# Debugger_V0_4.net
KiCad netlist of a schematic drawn in EAGLE
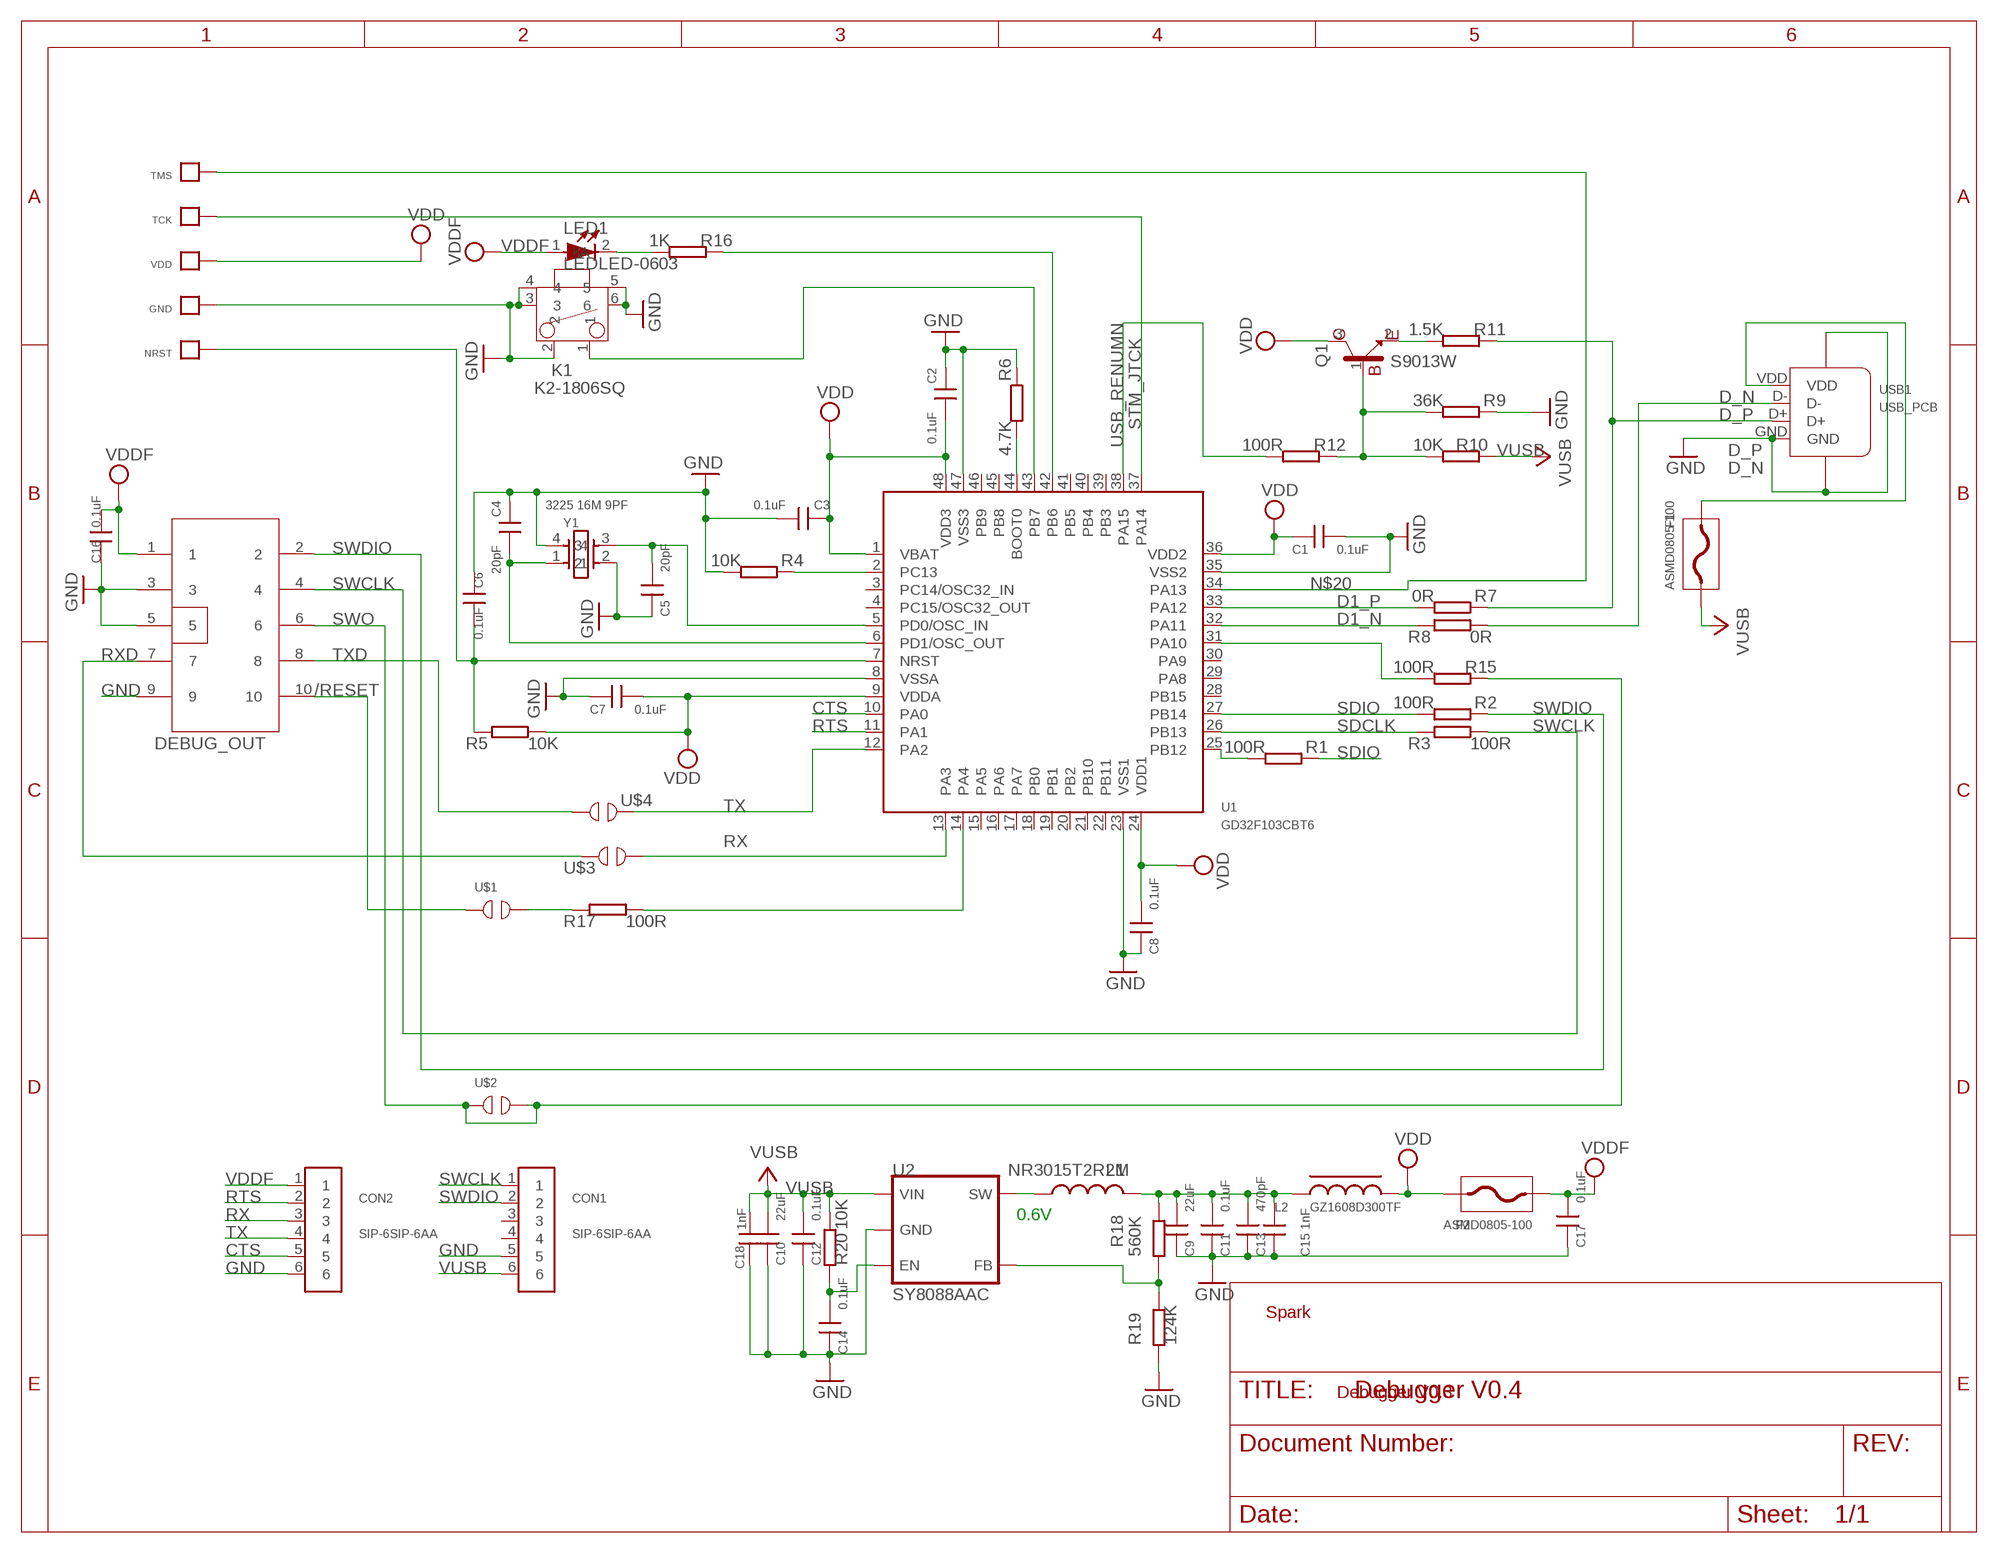
[diagram p0: schematic, sheet 1]

(export (version "E")
  (design (tool "Eeschema 10.0.6"))
  (components
    (comp (ref "C1")
      (value "0.1uF")
      (footprint "eagle-import:C0402")
      (libsource (lib "eagle-import") (part "CAP0402A"))
    )
    (comp (ref "C2")
      (value "0.1uF")
      (footprint "eagle-import:C0402")
      (libsource (lib "eagle-import") (part "CAP0402A"))
    )
    (comp (ref "C3")
      (value "0.1uF")
      (footprint "eagle-import:C0402")
      (libsource (lib "eagle-import") (part "CAP0402A"))
    )
    (comp (ref "C4")
      (value "20pF")
      (footprint "eagle-import:C0402")
      (libsource (lib "eagle-import") (part "CAP0402A"))
    )
    (comp (ref "C5")
      (value "20pF")
      (footprint "eagle-import:C0402")
      (libsource (lib "eagle-import") (part "CAP0402A"))
    )
    (comp (ref "C6")
      (value "0.1uF")
      (footprint "eagle-import:C0402")
      (libsource (lib "eagle-import") (part "CAP0402A"))
    )
    (comp (ref "C7")
      (value "0.1uF")
      (footprint "eagle-import:C0402")
      (libsource (lib "eagle-import") (part "CAP0402A"))
    )
    (comp (ref "C8")
      (value "0.1uF")
      (footprint "eagle-import:C0402")
      (libsource (lib "eagle-import") (part "CAP0402A"))
    )
    (comp (ref "C9")
      (value "22uF")
      (footprint "eagle-import:C0805")
      (libsource (lib "eagle-import") (part "CAPC0805"))
    )
    (comp (ref "C10")
      (value "22uF")
      (footprint "eagle-import:C0805")
      (libsource (lib "eagle-import") (part "CAPC0805"))
    )
    (comp (ref "C11")
      (value "0.1uF")
      (footprint "eagle-import:C0402")
      (libsource (lib "eagle-import") (part "CAP0402A"))
    )
    (comp (ref "C12")
      (value "0.1uF")
      (footprint "eagle-import:C0402")
      (libsource (lib "eagle-import") (part "CAP0402A"))
    )
    (comp (ref "C13")
      (value "470pF")
      (footprint "eagle-import:C0402")
      (libsource (lib "eagle-import") (part "CAP0402A"))
    )
    (comp (ref "C14")
      (value "0.1uF")
      (footprint "eagle-import:C0402")
      (libsource (lib "eagle-import") (part "CAP0402A"))
    )
    (comp (ref "C15")
      (value "1nF")
      (footprint "eagle-import:C0402")
      (libsource (lib "eagle-import") (part "CAP0402A"))
    )
    (comp (ref "C16")
      (value "0.1uF")
      (footprint "eagle-import:C0402")
      (libsource (lib "eagle-import") (part "CAP0402A"))
    )
    (comp (ref "C17")
      (value "0.1uF")
      (footprint "eagle-import:C0402")
      (libsource (lib "eagle-import") (part "CAP0402A"))
    )
    (comp (ref "C18")
      (value "1nF")
      (footprint "eagle-import:C0402")
      (libsource (lib "eagle-import") (part "CAP0402A"))
    )
    (comp (ref "CON1")
      (value "SIP-6SIP-6AA")
      (footprint "eagle-import:PAIZHEN6P_2.54AA")
      (libsource (lib "eagle-import") (part "SIP-6SIP-6AA"))
    )
    (comp (ref "CON2")
      (value "SIP-6SIP-6AA")
      (footprint "eagle-import:PAIZHEN6P_2.54AA")
      (libsource (lib "eagle-import") (part "SIP-6SIP-6AA"))
    )
    (comp (ref "DEBUG_OUT")
      (value "CON5X2")
      (footprint "eagle-import:CON5X2_1.27")
      (libsource (lib "eagle-import") (part "CON5X2"))
    )
    (comp (ref "F1")
      (value "ASMD0805-100")
      (footprint "eagle-import:F0805")
      (libsource (lib "eagle-import") (part "FUSE"))
    )
    (comp (ref "F2")
      (value "ASMD0805-100")
      (footprint "eagle-import:F0805")
      (libsource (lib "eagle-import") (part "FUSE"))
    )
    (comp (ref "GND")
      (value "TPTP")
      (footprint "eagle-import:TP")
      (libsource (lib "eagle-import") (part "TPTP"))
    )
    (comp (ref "K1")
      (value "K2-1806SQ")
      (footprint "eagle-import:K2-1806C")
      (libsource (lib "eagle-import") (part "K2-1806C"))
    )
    (comp (ref "L1")
      (value "NR3015T2R2M")
      (footprint "eagle-import:INDUCTOR-NR3015")
      (libsource (lib "eagle-import") (part "INDUCTORB"))
    )
    (comp (ref "L2")
      (value "GZ1608D300TF")
      (footprint "eagle-import:R-0603A")
      (libsource (lib "eagle-import") (part "L"))
    )
    (comp (ref "LED1")
      (value "LEDLED-0603")
      (footprint "eagle-import:LED-0603")
      (libsource (lib "eagle-import") (part "LEDLED-0603"))
    )
    (comp (ref "NRST")
      (value "TPTP")
      (footprint "eagle-import:TP")
      (libsource (lib "eagle-import") (part "TPTP"))
    )
    (comp (ref "Q1")
      (value "S9013W")
      (footprint "eagle-import:SOT-323")
      (libsource (lib "eagle-import") (part "NPNSOT-323"))
    )
    (comp (ref "R1")
      (value "100R")
      (footprint "eagle-import:R-0402S")
      (libsource (lib "eagle-import") (part "RES0402S"))
    )
    (comp (ref "R2")
      (value "100R")
      (footprint "eagle-import:R-0402S")
      (libsource (lib "eagle-import") (part "RES0402S"))
    )
    (comp (ref "R3")
      (value "100R")
      (footprint "eagle-import:R-0402S")
      (libsource (lib "eagle-import") (part "RES0402S"))
    )
    (comp (ref "R4")
      (value "10K")
      (footprint "eagle-import:R-0402S")
      (libsource (lib "eagle-import") (part "RES0402S"))
    )
    (comp (ref "R5")
      (value "10K")
      (footprint "eagle-import:R-0402S")
      (libsource (lib "eagle-import") (part "RES0402S"))
    )
    (comp (ref "R6")
      (value "4.7K")
      (footprint "eagle-import:R-0402S")
      (libsource (lib "eagle-import") (part "RES0402S"))
    )
    (comp (ref "R7")
      (value "0R")
      (footprint "eagle-import:R-0402S")
      (libsource (lib "eagle-import") (part "RES0402S"))
    )
    (comp (ref "R8")
      (value "0R")
      (footprint "eagle-import:R-0402S")
      (libsource (lib "eagle-import") (part "RES0402S"))
    )
    (comp (ref "R9")
      (value "36K")
      (footprint "eagle-import:R-0402S")
      (libsource (lib "eagle-import") (part "RES0402S"))
    )
    (comp (ref "R10")
      (value "10K")
      (footprint "eagle-import:R-0402S")
      (libsource (lib "eagle-import") (part "RES0402S"))
    )
    (comp (ref "R11")
      (value "1.5K")
      (footprint "eagle-import:R-0402S")
      (libsource (lib "eagle-import") (part "RES0402S"))
    )
    (comp (ref "R12")
      (value "100R")
      (footprint "eagle-import:R-0402S")
      (libsource (lib "eagle-import") (part "RES0402S"))
    )
    (comp (ref "R15")
      (value "100R")
      (footprint "eagle-import:R-0402S")
      (libsource (lib "eagle-import") (part "RES0402S"))
    )
    (comp (ref "R16")
      (value "1K")
      (footprint "eagle-import:R-0402S")
      (libsource (lib "eagle-import") (part "RES0402S"))
    )
    (comp (ref "R17")
      (value "100R")
      (footprint "eagle-import:R-0402S")
      (libsource (lib "eagle-import") (part "RES0402S"))
    )
    (comp (ref "R18")
      (value "560K")
      (footprint "eagle-import:R-0402S")
      (libsource (lib "eagle-import") (part "RES0402S"))
    )
    (comp (ref "R19")
      (value "124K")
      (footprint "eagle-import:R-0402S")
      (libsource (lib "eagle-import") (part "RES0402S"))
    )
    (comp (ref "R20")
      (value "10K")
      (footprint "eagle-import:R-0402S")
      (libsource (lib "eagle-import") (part "RES0402S"))
    )
    (comp (ref "TCK")
      (value "TPTP")
      (footprint "eagle-import:TP")
      (libsource (lib "eagle-import") (part "TPTP"))
    )
    (comp (ref "TMS")
      (value "TPTP")
      (footprint "eagle-import:TP")
      (libsource (lib "eagle-import") (part "TPTP"))
    )
    (comp (ref "U$1")
      (value "TP_OPEN")
      (footprint "eagle-import:TP_OPEN")
      (libsource (lib "eagle-import") (part "TP_OPEN"))
    )
    (comp (ref "U$2")
      (value "TP_OPEN")
      (footprint "eagle-import:TP_OPEN")
      (libsource (lib "eagle-import") (part "TP_OPEN"))
    )
    (comp (ref "U$3")
      (value "TP_OPEN")
      (footprint "eagle-import:TP_OPEN")
      (libsource (lib "eagle-import") (part "TP_OPEN"))
    )
    (comp (ref "U$4")
      (value "TP_OPEN")
      (footprint "eagle-import:TP_OPEN")
      (libsource (lib "eagle-import") (part "TP_OPEN"))
    )
    (comp (ref "U$6")
      (value "SPARK_LOGO..")
      (footprint "eagle-import:SPARK_LOGO")
      (libsource (lib "eagle-import") (part "SPARK_LOGO.."))
    )
    (comp (ref "U1")
      (value "GD32F103CBT6")
      (footprint "eagle-import:LQFP-48-7X7")
      (libsource (lib "eagle-import") (part "STM32F103LQFP48"))
    )
    (comp (ref "U2")
      (value "SY8088AAC")
      (footprint "eagle-import:SOT23-5L")
      (libsource (lib "eagle-import") (part "AX3701ABA"))
    )
    (comp (ref "USB1")
      (value "USB_PCB")
      (footprint "eagle-import:USB_PCB")
      (libsource (lib "eagle-import") (part "USB_PCB"))
    )
    (comp (ref "VDD")
      (value "TPTP")
      (footprint "eagle-import:TP")
      (libsource (lib "eagle-import") (part "TPTP"))
    )
    (comp (ref "Y1")
      (value "3225 16M 9PF")
      (footprint "eagle-import:CRY_3225_SMT")
      (libsource (lib "eagle-import") (part "CRY-3225CRY-3225"))
    )
  )
  (nets
    (net (code "1") (name "/CTS") (class "Default")
      (node (ref "CON2") (pin "5") (pinfunction "5_5") (pintype "bidirectional"))
      (node (ref "U1") (pin "10") (pinfunction "PA0_10") (pintype "bidirectional"))
    )
    (net (code "2") (name "/D1_N") (class "Default")
      (node (ref "R8") (pin "1") (pinfunction "1_1") (pintype "bidirectional"))
      (node (ref "U1") (pin "32") (pinfunction "PA11_32") (pintype "bidirectional"))
    )
    (net (code "3") (name "/D1_P") (class "Default")
      (node (ref "R7") (pin "2") (pinfunction "2_2") (pintype "bidirectional"))
      (node (ref "U1") (pin "33") (pinfunction "PA12_33") (pintype "bidirectional"))
    )
    (net (code "4") (name "/D_N") (class "Default")
      (node (ref "R8") (pin "2") (pinfunction "2_2") (pintype "bidirectional"))
      (node (ref "USB1") (pin "D-") (pinfunction "D-_D-") (pintype "bidirectional"))
    )
    (net (code "5") (name "/D_P") (class "Default")
      (node (ref "R11") (pin "1") (pinfunction "1_1") (pintype "bidirectional"))
      (node (ref "R7") (pin "1") (pinfunction "1_1") (pintype "bidirectional"))
      (node (ref "USB1") (pin "D+") (pinfunction "D+_D+") (pintype "bidirectional"))
    )
    (net (code "6") (name "/N$20") (class "Default")
      (node (ref "TMS") (pin "P$1") (pinfunction "1_P$1") (pintype "bidirectional"))
      (node (ref "U1") (pin "34") (pinfunction "PA13_34") (pintype "bidirectional"))
    )
    (net (code "7") (name "/RTS") (class "Default")
      (node (ref "CON2") (pin "2") (pinfunction "2_2") (pintype "bidirectional"))
      (node (ref "U1") (pin "11") (pinfunction "PA1_11") (pintype "bidirectional"))
    )
    (net (code "8") (name "/RX") (class "Default")
      (node (ref "CON2") (pin "3") (pinfunction "3_3") (pintype "bidirectional"))
      (node (ref "U$3") (pin "2") (pinfunction "2_2") (pintype "bidirectional"))
      (node (ref "U1") (pin "13") (pinfunction "PA3_13") (pintype "bidirectional"))
    )
    (net (code "9") (name "/RXD") (class "Default")
      (node (ref "DEBUG_OUT") (pin "7") (pinfunction "7_7") (pintype "bidirectional"))
      (node (ref "U$3") (pin "1") (pinfunction "1_1") (pintype "bidirectional"))
    )
    (net (code "10") (name "/SDCLK") (class "Default")
      (node (ref "R3") (pin "1") (pinfunction "1_1") (pintype "bidirectional"))
      (node (ref "U1") (pin "26") (pinfunction "PB13_26") (pintype "bidirectional"))
    )
    (net (code "11") (name "/SDIO") (class "Default")
      (node (ref "R1") (pin "1") (pinfunction "1_1") (pintype "bidirectional"))
      (node (ref "R2") (pin "2") (pinfunction "2_2") (pintype "bidirectional"))
      (node (ref "U1") (pin "27") (pinfunction "PB14_27") (pintype "bidirectional"))
    )
    (net (code "12") (name "/STM_JTCK") (class "Default")
      (node (ref "TCK") (pin "P$1") (pinfunction "1_P$1") (pintype "bidirectional"))
      (node (ref "U1") (pin "37") (pinfunction "PA14_37") (pintype "bidirectional"))
    )
    (net (code "13") (name "/SWCLK") (class "Default")
      (node (ref "CON1") (pin "1") (pinfunction "1_1") (pintype "bidirectional"))
      (node (ref "DEBUG_OUT") (pin "4") (pinfunction "4_4") (pintype "bidirectional"))
      (node (ref "R3") (pin "2") (pinfunction "2_2") (pintype "bidirectional"))
    )
    (net (code "14") (name "/SWDIO") (class "Default")
      (node (ref "CON1") (pin "2") (pinfunction "2_2") (pintype "bidirectional"))
      (node (ref "DEBUG_OUT") (pin "2") (pinfunction "2_2") (pintype "bidirectional"))
      (node (ref "R2") (pin "1") (pinfunction "1_1") (pintype "bidirectional"))
    )
    (net (code "15") (name "/SWO") (class "Default")
      (node (ref "DEBUG_OUT") (pin "6") (pinfunction "6_6") (pintype "bidirectional"))
      (node (ref "R15") (pin "1") (pinfunction "1_1") (pintype "bidirectional"))
      (node (ref "U$2") (pin "1") (pinfunction "1_1") (pintype "bidirectional"))
      (node (ref "U$2") (pin "2") (pinfunction "2_2") (pintype "bidirectional"))
    )
    (net (code "16") (name "/TX") (class "Default")
      (node (ref "CON2") (pin "4") (pinfunction "4_4") (pintype "bidirectional"))
      (node (ref "U$4") (pin "1") (pinfunction "1_1") (pintype "bidirectional"))
      (node (ref "U1") (pin "12") (pinfunction "PA2_12") (pintype "bidirectional"))
    )
    (net (code "17") (name "/TXD") (class "Default")
      (node (ref "DEBUG_OUT") (pin "8") (pinfunction "8_8") (pintype "bidirectional"))
      (node (ref "U$4") (pin "2") (pinfunction "2_2") (pintype "bidirectional"))
    )
    (net (code "18") (name "/USB_RENUMN") (class "Default")
      (node (ref "R12") (pin "2") (pinfunction "2_2") (pintype "bidirectional"))
      (node (ref "U1") (pin "38") (pinfunction "PA15_38") (pintype "bidirectional"))
    )
    (net (code "19") (name "/{slash}RESET") (class "Default")
      (node (ref "DEBUG_OUT") (pin "10") (pinfunction "10_10") (pintype "bidirectional"))
      (node (ref "U$1") (pin "1") (pinfunction "1_1") (pintype "bidirectional"))
    )
    (net (code "20") (name "GND") (class "Default")
      (node (ref "C1") (pin "1") (pinfunction "1_1") (pintype "bidirectional"))
      (node (ref "C10") (pin "2") (pinfunction "2_2") (pintype "bidirectional"))
      (node (ref "C11") (pin "2") (pinfunction "2_2") (pintype "bidirectional"))
      (node (ref "C12") (pin "2") (pinfunction "2_2") (pintype "bidirectional"))
      (node (ref "C13") (pin "2") (pinfunction "2_2") (pintype "bidirectional"))
      (node (ref "C14") (pin "2") (pinfunction "2_2") (pintype "bidirectional"))
      (node (ref "C15") (pin "2") (pinfunction "2_2") (pintype "bidirectional"))
      (node (ref "C16") (pin "2") (pinfunction "2_2") (pintype "bidirectional"))
      (node (ref "C17") (pin "2") (pinfunction "2_2") (pintype "bidirectional"))
      (node (ref "C18") (pin "2") (pinfunction "2_2") (pintype "bidirectional"))
      (node (ref "C2") (pin "2") (pinfunction "2_2") (pintype "bidirectional"))
      (node (ref "C3") (pin "1") (pinfunction "1_1") (pintype "bidirectional"))
      (node (ref "C4") (pin "2") (pinfunction "2_2") (pintype "bidirectional"))
      (node (ref "C5") (pin "2") (pinfunction "2_2") (pintype "bidirectional"))
      (node (ref "C6") (pin "2") (pinfunction "2_2") (pintype "bidirectional"))
      (node (ref "C7") (pin "2") (pinfunction "2_2") (pintype "bidirectional"))
      (node (ref "C8") (pin "2") (pinfunction "2_2") (pintype "bidirectional"))
      (node (ref "C9") (pin "2") (pinfunction "2_2") (pintype "bidirectional"))
      (node (ref "CON1") (pin "5") (pinfunction "5_5") (pintype "bidirectional"))
      (node (ref "CON2") (pin "6") (pinfunction "6_6") (pintype "bidirectional"))
      (node (ref "DEBUG_OUT") (pin "3") (pinfunction "3_3") (pintype "bidirectional"))
      (node (ref "DEBUG_OUT") (pin "5") (pinfunction "5_5") (pintype "bidirectional"))
      (node (ref "DEBUG_OUT") (pin "9") (pinfunction "9_9") (pintype "bidirectional"))
      (node (ref "GND") (pin "P$1") (pinfunction "1_P$1") (pintype "bidirectional"))
      (node (ref "K1") (pin "2") (pinfunction "2_2") (pintype "bidirectional"))
      (node (ref "K1") (pin "3") (pinfunction "3_3") (pintype "bidirectional"))
      (node (ref "K1") (pin "4") (pinfunction "4_4") (pintype "bidirectional"))
      (node (ref "K1") (pin "5") (pinfunction "5_5") (pintype "bidirectional"))
      (node (ref "K1") (pin "6") (pinfunction "6_6") (pintype "bidirectional"))
      (node (ref "R19") (pin "1") (pinfunction "1_1") (pintype "bidirectional"))
      (node (ref "R4") (pin "2") (pinfunction "2_2") (pintype "bidirectional"))
      (node (ref "R6") (pin "1") (pinfunction "1_1") (pintype "bidirectional"))
      (node (ref "R9") (pin "1") (pinfunction "1_1") (pintype "bidirectional"))
      (node (ref "U1") (pin "23") (pinfunction "VSS1_23") (pintype "bidirectional"))
      (node (ref "U1") (pin "35") (pinfunction "VSS2_35") (pintype "bidirectional"))
      (node (ref "U1") (pin "47") (pinfunction "VSS3_47") (pintype "bidirectional"))
      (node (ref "U1") (pin "8") (pinfunction "VSSA_8") (pintype "bidirectional"))
      (node (ref "U2") (pin "2") (pinfunction "GND_2") (pintype "power_in"))
      (node (ref "USB1") (pin "GND") (pinfunction "GND_GND") (pintype "bidirectional"))
      (node (ref "USB1") (pin "GND1") (pinfunction "GND1_GND1") (pintype "power_in"))
      (node (ref "USB1") (pin "GND2") (pinfunction "GND2_GND2") (pintype "bidirectional"))
      (node (ref "Y1") (pin "2") (pinfunction "2_2") (pintype "bidirectional"))
      (node (ref "Y1") (pin "4") (pinfunction "4_4") (pintype "bidirectional"))
    )
    (net (code "21") (name "Net-(C11-Pad1)") (class "Default")
      (node (ref "C11") (pin "1") (pinfunction "1_1") (pintype "bidirectional"))
      (node (ref "C13") (pin "1") (pinfunction "1_1") (pintype "bidirectional"))
      (node (ref "C15") (pin "1") (pinfunction "1_1") (pintype "bidirectional"))
      (node (ref "C9") (pin "1") (pinfunction "1_1") (pintype "bidirectional"))
      (node (ref "L1") (pin "2") (pinfunction "2_2") (pintype "passive"))
      (node (ref "L2") (pin "1") (pinfunction "1_1") (pintype "bidirectional"))
      (node (ref "R18") (pin "2") (pinfunction "2_2") (pintype "bidirectional"))
    )
    (net (code "22") (name "Net-(F1-2)") (class "Default")
      (node (ref "F1") (pin "P$2") (pinfunction "2_P$2") (pintype "bidirectional"))
      (node (ref "USB1") (pin "VDD") (pinfunction "VDD_VDD") (pintype "bidirectional"))
    )
    (net (code "23") (name "Net-(LED1-K)") (class "Default")
      (node (ref "LED1") (pin "2") (pinfunction "K_2") (pintype "bidirectional"))
      (node (ref "R16") (pin "2") (pinfunction "2_2") (pintype "bidirectional"))
    )
    (net (code "24") (name "Net-(NRST-1)") (class "Default")
      (node (ref "C6") (pin "1") (pinfunction "1_1") (pintype "bidirectional"))
      (node (ref "NRST") (pin "P$1") (pinfunction "1_P$1") (pintype "bidirectional"))
      (node (ref "R5") (pin "1") (pinfunction "1_1") (pintype "bidirectional"))
      (node (ref "U1") (pin "7") (pinfunction "NRST_7") (pintype "bidirectional"))
    )
    (net (code "25") (name "Net-(Q1-B)") (class "Default")
      (node (ref "Q1") (pin "1") (pinfunction "B_1") (pintype "bidirectional"))
      (node (ref "R10") (pin "2") (pinfunction "2_2") (pintype "bidirectional"))
      (node (ref "R12") (pin "1") (pinfunction "1_1") (pintype "bidirectional"))
      (node (ref "R9") (pin "2") (pinfunction "2_2") (pintype "bidirectional"))
    )
    (net (code "26") (name "Net-(Q1-E)") (class "Default")
      (node (ref "Q1") (pin "2") (pinfunction "E_2") (pintype "bidirectional"))
      (node (ref "R11") (pin "2") (pinfunction "2_2") (pintype "bidirectional"))
    )
    (net (code "27") (name "Net-(R17-Pad1)") (class "Default")
      (node (ref "R17") (pin "1") (pinfunction "1_1") (pintype "bidirectional"))
      (node (ref "U$1") (pin "2") (pinfunction "2_2") (pintype "bidirectional"))
    )
    (net (code "28") (name "Net-(U1-BOOT0)") (class "Default")
      (node (ref "R6") (pin "2") (pinfunction "2_2") (pintype "bidirectional"))
      (node (ref "U1") (pin "44") (pinfunction "BOOT0_44") (pintype "bidirectional"))
    )
    (net (code "29") (name "Net-(U1-PA4)") (class "Default")
      (node (ref "R17") (pin "2") (pinfunction "2_2") (pintype "bidirectional"))
      (node (ref "U1") (pin "14") (pinfunction "PA4_14") (pintype "bidirectional"))
    )
    (net (code "30") (name "Net-(U1-PA10)") (class "Default")
      (node (ref "R15") (pin "2") (pinfunction "2_2") (pintype "bidirectional"))
      (node (ref "U1") (pin "31") (pinfunction "PA10_31") (pintype "bidirectional"))
    )
    (net (code "31") (name "Net-(U1-PB6)") (class "Default")
      (node (ref "R16") (pin "1") (pinfunction "1_1") (pintype "bidirectional"))
      (node (ref "U1") (pin "42") (pinfunction "PB6_42") (pintype "bidirectional"))
    )
    (net (code "32") (name "Net-(U1-PB7)") (class "Default")
      (node (ref "K1") (pin "1") (pinfunction "1_1") (pintype "bidirectional"))
      (node (ref "U1") (pin "43") (pinfunction "PB7_43") (pintype "bidirectional"))
    )
    (net (code "33") (name "Net-(U1-PB12)") (class "Default")
      (node (ref "R1") (pin "2") (pinfunction "2_2") (pintype "bidirectional"))
      (node (ref "U1") (pin "25") (pinfunction "PB12_25") (pintype "bidirectional"))
    )
    (net (code "34") (name "Net-(U1-PC13)") (class "Default")
      (node (ref "R4") (pin "1") (pinfunction "1_1") (pintype "bidirectional"))
      (node (ref "U1") (pin "2") (pinfunction "PC13_2") (pintype "bidirectional"))
    )
    (net (code "35") (name "Net-(U1-PD0{slash}OSC_IN)") (class "Default")
      (node (ref "C5") (pin "1") (pinfunction "1_1") (pintype "bidirectional"))
      (node (ref "U1") (pin "5") (pinfunction "PD0/OSC_IN_5") (pintype "bidirectional"))
      (node (ref "Y1") (pin "3") (pinfunction "3_3") (pintype "bidirectional"))
    )
    (net (code "36") (name "Net-(U1-PD1{slash}OSC_OUT)") (class "Default")
      (node (ref "C4") (pin "1") (pinfunction "1_1") (pintype "bidirectional"))
      (node (ref "U1") (pin "6") (pinfunction "PD1/OSC_OUT_6") (pintype "bidirectional"))
      (node (ref "Y1") (pin "1") (pinfunction "1_1") (pintype "bidirectional"))
    )
    (net (code "37") (name "Net-(U2-EN)") (class "Default")
      (node (ref "C14") (pin "1") (pinfunction "1_1") (pintype "bidirectional"))
      (node (ref "R20") (pin "1") (pinfunction "1_1") (pintype "bidirectional"))
      (node (ref "U2") (pin "1") (pinfunction "EN_1") (pintype "input"))
    )
    (net (code "38") (name "Net-(U2-FB)") (class "Default")
      (node (ref "R18") (pin "1") (pinfunction "1_1") (pintype "bidirectional"))
      (node (ref "R19") (pin "2") (pinfunction "2_2") (pintype "bidirectional"))
      (node (ref "U2") (pin "5") (pinfunction "FB_5") (pintype "input"))
    )
    (net (code "39") (name "Net-(U2-SW)") (class "Default")
      (node (ref "L1") (pin "1") (pinfunction "1_1") (pintype "passive"))
      (node (ref "U2") (pin "3") (pinfunction "SW_3") (pintype "output"))
    )
    (net (code "40") (name "VDD") (class "Default")
      (node (ref "C1") (pin "2") (pinfunction "2_2") (pintype "bidirectional"))
      (node (ref "C2") (pin "1") (pinfunction "1_1") (pintype "bidirectional"))
      (node (ref "C3") (pin "2") (pinfunction "2_2") (pintype "bidirectional"))
      (node (ref "C7") (pin "1") (pinfunction "1_1") (pintype "bidirectional"))
      (node (ref "C8") (pin "1") (pinfunction "1_1") (pintype "bidirectional"))
      (node (ref "F2") (pin "P$2") (pinfunction "2_P$2") (pintype "bidirectional"))
      (node (ref "L2") (pin "2") (pinfunction "2_2") (pintype "bidirectional"))
      (node (ref "Q1") (pin "3") (pinfunction "C_3") (pintype "bidirectional"))
      (node (ref "R5") (pin "2") (pinfunction "2_2") (pintype "bidirectional"))
      (node (ref "U1") (pin "1") (pinfunction "VBAT_1") (pintype "bidirectional"))
      (node (ref "U1") (pin "24") (pinfunction "VDD1_24") (pintype "bidirectional"))
      (node (ref "U1") (pin "36") (pinfunction "VDD2_36") (pintype "bidirectional"))
      (node (ref "U1") (pin "48") (pinfunction "VDD3_48") (pintype "bidirectional"))
      (node (ref "U1") (pin "9") (pinfunction "VDDA_9") (pintype "bidirectional"))
      (node (ref "VDD") (pin "P$1") (pinfunction "1_P$1") (pintype "bidirectional"))
    )
    (net (code "41") (name "VDDF") (class "Default")
      (node (ref "C16") (pin "1") (pinfunction "1_1") (pintype "bidirectional"))
      (node (ref "C17") (pin "1") (pinfunction "1_1") (pintype "bidirectional"))
      (node (ref "CON2") (pin "1") (pinfunction "1_1") (pintype "bidirectional"))
      (node (ref "DEBUG_OUT") (pin "1") (pinfunction "1_1") (pintype "bidirectional"))
      (node (ref "F2") (pin "P$1") (pinfunction "1_P$1") (pintype "bidirectional"))
      (node (ref "LED1") (pin "1") (pinfunction "A_1") (pintype "bidirectional"))
    )
    (net (code "42") (name "VUSB") (class "Default")
      (node (ref "C10") (pin "1") (pinfunction "1_1") (pintype "bidirectional"))
      (node (ref "C12") (pin "1") (pinfunction "1_1") (pintype "bidirectional"))
      (node (ref "C18") (pin "1") (pinfunction "1_1") (pintype "bidirectional"))
      (node (ref "CON1") (pin "6") (pinfunction "6_6") (pintype "bidirectional"))
      (node (ref "F1") (pin "P$1") (pinfunction "1_P$1") (pintype "bidirectional"))
      (node (ref "R10") (pin "1") (pinfunction "1_1") (pintype "bidirectional"))
      (node (ref "R20") (pin "2") (pinfunction "2_2") (pintype "bidirectional"))
      (node (ref "U2") (pin "4") (pinfunction "VIN_4") (pintype "input"))
    )
    (net (code "43") (name "unconnected-(CON1-Pad3)") (class "Default")
      (node (ref "CON1") (pin "3") (pinfunction "3_3") (pintype "bidirectional"))
    )
    (net (code "44") (name "unconnected-(CON1-Pad4)") (class "Default")
      (node (ref "CON1") (pin "4") (pinfunction "4_4") (pintype "bidirectional"))
    )
    (net (code "45") (name "unconnected-(U1-PA5-Pad15)") (class "Default")
      (node (ref "U1") (pin "15") (pinfunction "PA5_15") (pintype "bidirectional"))
    )
    (net (code "46") (name "unconnected-(U1-PA6-Pad16)") (class "Default")
      (node (ref "U1") (pin "16") (pinfunction "PA6_16") (pintype "bidirectional"))
    )
    (net (code "47") (name "unconnected-(U1-PA7-Pad17)") (class "Default")
      (node (ref "U1") (pin "17") (pinfunction "PA7_17") (pintype "bidirectional"))
    )
    (net (code "48") (name "unconnected-(U1-PA8-Pad29)") (class "Default")
      (node (ref "U1") (pin "29") (pinfunction "PA8_29") (pintype "bidirectional"))
    )
    (net (code "49") (name "unconnected-(U1-PA9-Pad30)") (class "Default")
      (node (ref "U1") (pin "30") (pinfunction "PA9_30") (pintype "bidirectional"))
    )
    (net (code "50") (name "unconnected-(U1-PB0-Pad18)") (class "Default")
      (node (ref "U1") (pin "18") (pinfunction "PB0_18") (pintype "bidirectional"))
    )
    (net (code "51") (name "unconnected-(U1-PB1-Pad19)") (class "Default")
      (node (ref "U1") (pin "19") (pinfunction "PB1_19") (pintype "bidirectional"))
    )
    (net (code "52") (name "unconnected-(U1-PB2-Pad20)") (class "Default")
      (node (ref "U1") (pin "20") (pinfunction "PB2_20") (pintype "bidirectional"))
    )
    (net (code "53") (name "unconnected-(U1-PB3-Pad39)") (class "Default")
      (node (ref "U1") (pin "39") (pinfunction "PB3_39") (pintype "bidirectional"))
    )
    (net (code "54") (name "unconnected-(U1-PB4-Pad40)") (class "Default")
      (node (ref "U1") (pin "40") (pinfunction "PB4_40") (pintype "bidirectional"))
    )
    (net (code "55") (name "unconnected-(U1-PB5-Pad41)") (class "Default")
      (node (ref "U1") (pin "41") (pinfunction "PB5_41") (pintype "bidirectional"))
    )
    (net (code "56") (name "unconnected-(U1-PB8-Pad45)") (class "Default")
      (node (ref "U1") (pin "45") (pinfunction "PB8_45") (pintype "bidirectional"))
    )
    (net (code "57") (name "unconnected-(U1-PB9-Pad46)") (class "Default")
      (node (ref "U1") (pin "46") (pinfunction "PB9_46") (pintype "bidirectional"))
    )
    (net (code "58") (name "unconnected-(U1-PB10-Pad21)") (class "Default")
      (node (ref "U1") (pin "21") (pinfunction "PB10_21") (pintype "bidirectional"))
    )
    (net (code "59") (name "unconnected-(U1-PB11-Pad22)") (class "Default")
      (node (ref "U1") (pin "22") (pinfunction "PB11_22") (pintype "bidirectional"))
    )
    (net (code "60") (name "unconnected-(U1-PB15-Pad28)") (class "Default")
      (node (ref "U1") (pin "28") (pinfunction "PB15_28") (pintype "bidirectional"))
    )
    (net (code "61") (name "unconnected-(U1-PC14{slash}OSC32_IN-Pad3)") (class "Default")
      (node (ref "U1") (pin "3") (pinfunction "PC14/OSC32_IN_3") (pintype "bidirectional"))
    )
    (net (code "62") (name "unconnected-(U1-PC15{slash}OSC32_OUT-Pad4)") (class "Default")
      (node (ref "U1") (pin "4") (pinfunction "PC15/OSC32_OUT_4") (pintype "bidirectional"))
    )
  )
)
